# v2_Sandwich_8_bit_waves.net
KiCad netlist of a schematic drawn in EAGLE
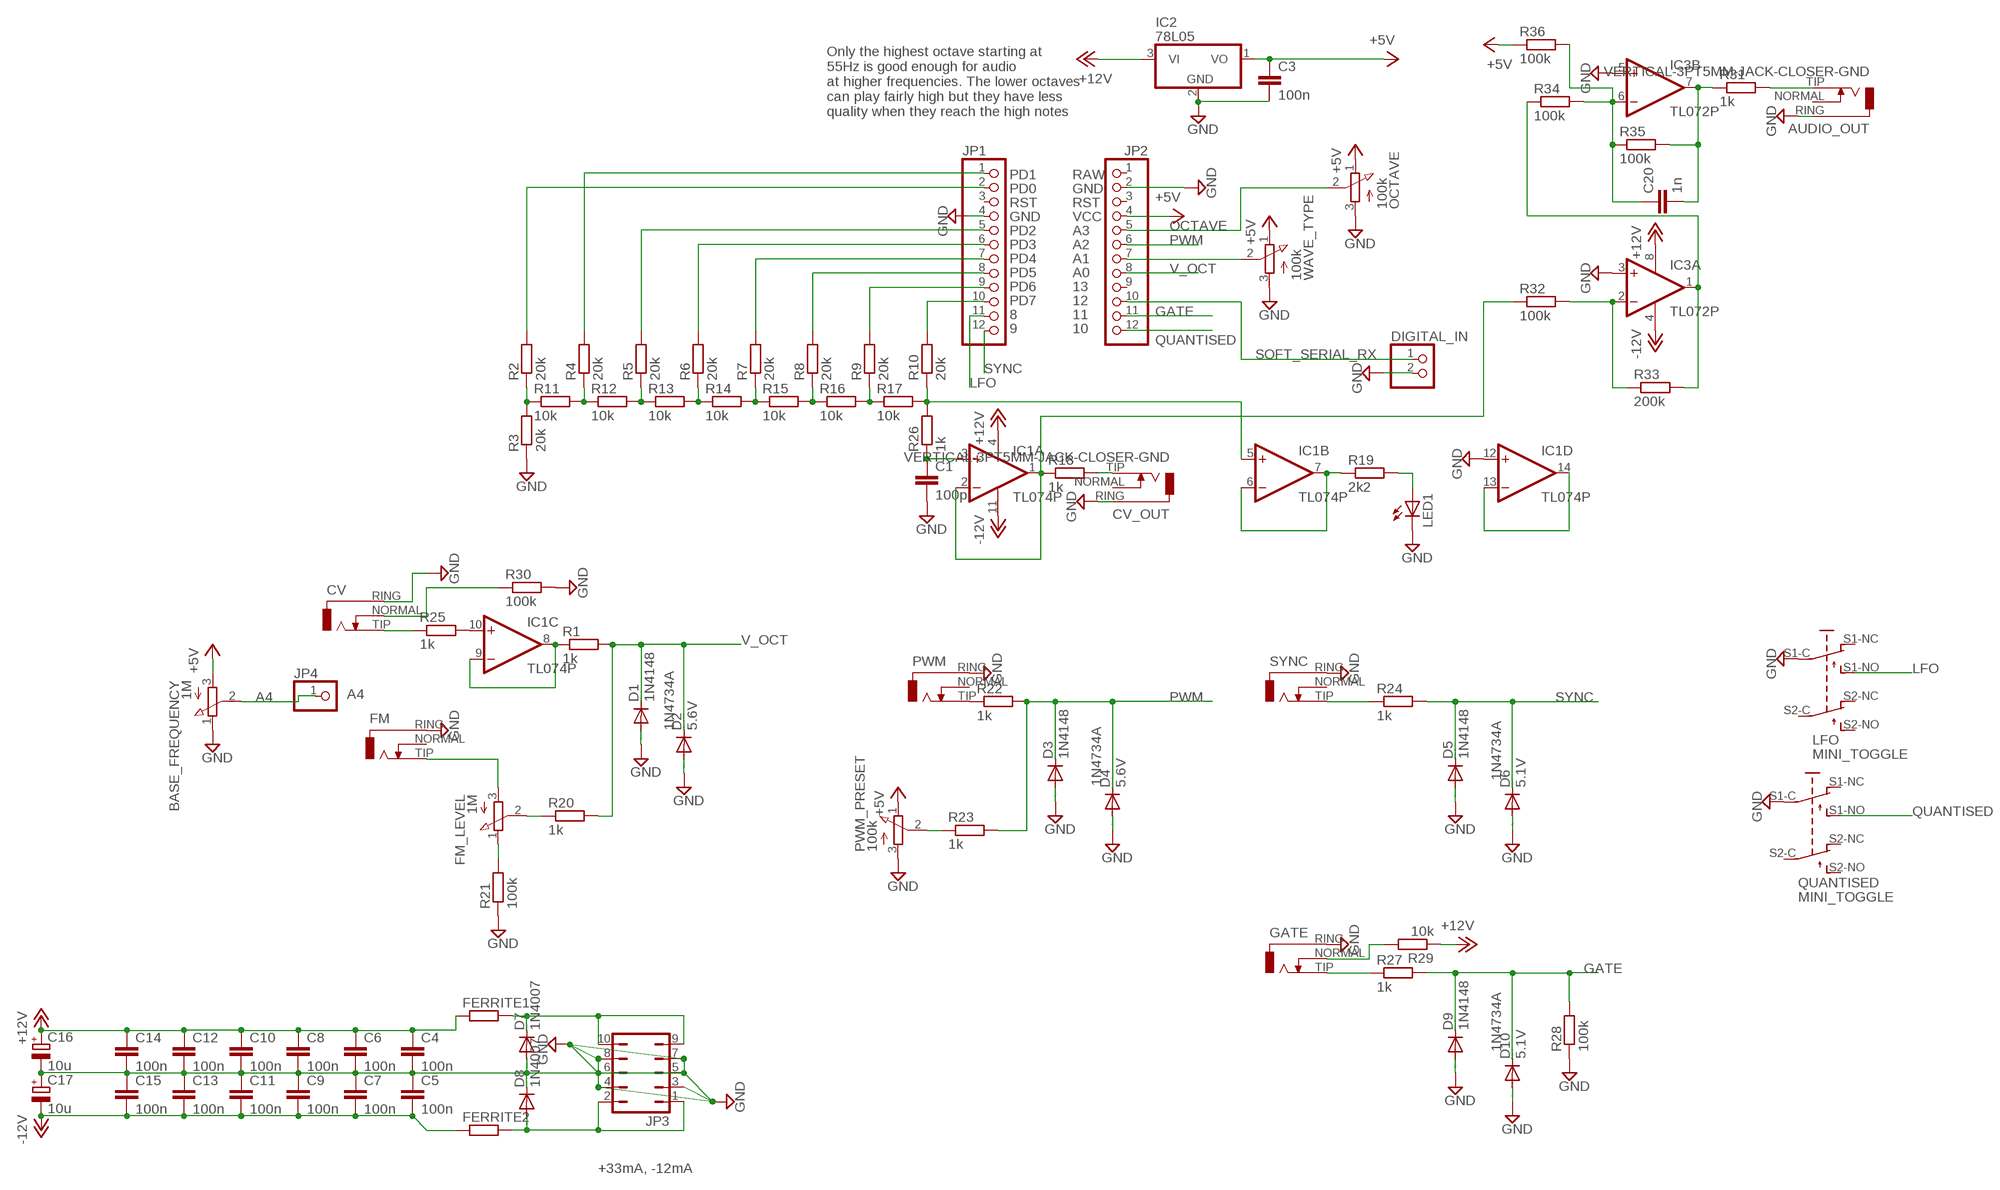
[diagram p0: schematic, sheet 1]

(export (version "E")
  (design (tool "Eeschema 10.0.6"))
  (components
    (comp (ref "AUDIO_OUT")
      (value "VERTICAL-3PT5MM-JACK-CLOSER-GND")
      (footprint "eagle-import:VERTICAL-3PT5MM-JACK-CLOSER-GND")
      (libsource (lib "eagle-import") (part "VERTICAL-3PT5MM-JACK-CLOSER-GND"))
    )
    (comp (ref "BASE_FREQUENCY")
      (value "1M")
      (footprint "eagle-import:EVUF")
      (libsource (lib "eagle-import") (part "9MM_VERT_POT"))
    )
    (comp (ref "C1")
      (value "100p")
      (footprint "eagle-import:C050-024X044")
      (libsource (lib "eagle-import") (part "C-EU050-024X044"))
    )
    (comp (ref "C3")
      (value "100n")
      (footprint "eagle-import:C050-024X044")
      (libsource (lib "eagle-import") (part "C-EU050-024X044"))
    )
    (comp (ref "C4")
      (value "100n")
      (footprint "eagle-import:C050-024X044")
      (libsource (lib "eagle-import") (part "C-EU050-024X044"))
    )
    (comp (ref "C5")
      (value "100n")
      (footprint "eagle-import:C050-024X044")
      (libsource (lib "eagle-import") (part "C-EU050-024X044"))
    )
    (comp (ref "C6")
      (value "100n")
      (footprint "eagle-import:C050-024X044")
      (libsource (lib "eagle-import") (part "C-EU050-024X044"))
    )
    (comp (ref "C7")
      (value "100n")
      (footprint "eagle-import:C050-024X044")
      (libsource (lib "eagle-import") (part "C-EU050-024X044"))
    )
    (comp (ref "C8")
      (value "100n")
      (footprint "eagle-import:C050-024X044")
      (libsource (lib "eagle-import") (part "C-EU050-024X044"))
    )
    (comp (ref "C9")
      (value "100n")
      (footprint "eagle-import:C050-024X044")
      (libsource (lib "eagle-import") (part "C-EU050-024X044"))
    )
    (comp (ref "C10")
      (value "100n")
      (footprint "eagle-import:C050-024X044")
      (libsource (lib "eagle-import") (part "C-EU050-024X044"))
    )
    (comp (ref "C11")
      (value "100n")
      (footprint "eagle-import:C050-024X044")
      (libsource (lib "eagle-import") (part "C-EU050-024X044"))
    )
    (comp (ref "C12")
      (value "100n")
      (footprint "eagle-import:C050-024X044")
      (libsource (lib "eagle-import") (part "C-EU050-024X044"))
    )
    (comp (ref "C13")
      (value "100n")
      (footprint "eagle-import:C050-024X044")
      (libsource (lib "eagle-import") (part "C-EU050-024X044"))
    )
    (comp (ref "C14")
      (value "100n")
      (footprint "eagle-import:C050-024X044")
      (libsource (lib "eagle-import") (part "C-EU050-024X044"))
    )
    (comp (ref "C15")
      (value "100n")
      (footprint "eagle-import:C050-024X044")
      (libsource (lib "eagle-import") (part "C-EU050-024X044"))
    )
    (comp (ref "C16")
      (value "10u")
      (footprint "eagle-import:E2,5-5")
      (libsource (lib "eagle-import") (part "CPOL-EUE2.5-5"))
    )
    (comp (ref "C17")
      (value "10u")
      (footprint "eagle-import:E2,5-5")
      (libsource (lib "eagle-import") (part "CPOL-EUE2.5-5"))
    )
    (comp (ref "C20")
      (value "1n")
      (footprint "eagle-import:C050-024X044")
      (libsource (lib "eagle-import") (part "C-EU050-024X044"))
    )
    (comp (ref "CV")
      (value "VERTICAL-3PT5MM-JACK-CLOSER-GND")
      (footprint "eagle-import:VERTICAL-3PT5MM-JACK-CLOSER-GND")
      (libsource (lib "eagle-import") (part "VERTICAL-3PT5MM-JACK-CLOSER-GND"))
    )
    (comp (ref "CV_OUT")
      (value "VERTICAL-3PT5MM-JACK-CLOSER-GND")
      (footprint "eagle-import:VERTICAL-3PT5MM-JACK-CLOSER-GND")
      (libsource (lib "eagle-import") (part "VERTICAL-3PT5MM-JACK-CLOSER-GND"))
    )
    (comp (ref "D1")
      (value "1N4148")
      (footprint "eagle-import:D-6.35")
      (libsource (lib "eagle-import") (part "1N914"))
    )
    (comp (ref "D2")
      (value "5.6V")
      (footprint "eagle-import:DO41-10")
      (libsource (lib "eagle-import") (part "1N4004"))
    )
    (comp (ref "D3")
      (value "1N4148")
      (footprint "eagle-import:D-6.35")
      (libsource (lib "eagle-import") (part "1N914"))
    )
    (comp (ref "D4")
      (value "5.6V")
      (footprint "eagle-import:DO41-10")
      (libsource (lib "eagle-import") (part "1N4004"))
    )
    (comp (ref "D5")
      (value "1N4148")
      (footprint "eagle-import:D-6.35")
      (libsource (lib "eagle-import") (part "1N914"))
    )
    (comp (ref "D6")
      (value "5.1V")
      (footprint "eagle-import:DO41-10")
      (libsource (lib "eagle-import") (part "1N4004"))
    )
    (comp (ref "D7")
      (value "1N4007")
      (footprint "eagle-import:DO41-10")
      (libsource (lib "eagle-import") (part "1N4004"))
    )
    (comp (ref "D8")
      (value "1N4007")
      (footprint "eagle-import:DO41-10")
      (libsource (lib "eagle-import") (part "1N4004"))
    )
    (comp (ref "D9")
      (value "1N4148")
      (footprint "eagle-import:D-6.35")
      (libsource (lib "eagle-import") (part "1N914"))
    )
    (comp (ref "D10")
      (value "5.1V")
      (footprint "eagle-import:DO41-10")
      (libsource (lib "eagle-import") (part "1N4004"))
    )
    (comp (ref "DIGITAL_IN")
      (value "PINHD-1X2")
      (footprint "eagle-import:1X02")
      (libsource (lib "eagle-import") (part "PINHD-1X2"))
    )
    (comp (ref "FERRITE1")
      (value "R-EU_0204/7")
      (footprint "eagle-import:0204_7")
      (libsource (lib "eagle-import") (part "R-EU_0204/7"))
    )
    (comp (ref "FERRITE2")
      (value "R-EU_0204/7")
      (footprint "eagle-import:0204_7")
      (libsource (lib "eagle-import") (part "R-EU_0204/7"))
    )
    (comp (ref "FM")
      (value "VERTICAL-3PT5MM-JACK-CLOSER-GND")
      (footprint "eagle-import:VERTICAL-3PT5MM-JACK-CLOSER-GND")
      (libsource (lib "eagle-import") (part "VERTICAL-3PT5MM-JACK-CLOSER-GND"))
    )
    (comp (ref "FM_LEVEL")
      (value "1M")
      (footprint "eagle-import:EVUF")
      (libsource (lib "eagle-import") (part "9MM_VERT_POT"))
    )
    (comp (ref "GATE")
      (value "VERTICAL-3PT5MM-JACK-CLOSER-GND")
      (footprint "eagle-import:VERTICAL-3PT5MM-JACK-CLOSER-GND")
      (libsource (lib "eagle-import") (part "VERTICAL-3PT5MM-JACK-CLOSER-GND"))
    )
    (comp (ref "IC1")
      (value "TL074P")
      (footprint "eagle-import:DIL14")
      (libsource (lib "eagle-import") (part "TL074P"))
    )
    (comp (ref "IC2")
      (value "78L05")
      (footprint "eagle-import:TO92")
      (libsource (lib "eagle-import") (part "78ZL05"))
    )
    (comp (ref "IC3")
      (value "TL072P")
      (footprint "eagle-import:DIL08")
      (libsource (lib "eagle-import") (part "TL072P"))
    )
    (comp (ref "JP1")
      (value "PINHD-1X12")
      (footprint "eagle-import:1X12")
      (libsource (lib "eagle-import") (part "PINHD-1X12"))
    )
    (comp (ref "JP2")
      (value "PINHD-1X12")
      (footprint "eagle-import:1X12")
      (libsource (lib "eagle-import") (part "PINHD-1X12"))
    )
    (comp (ref "JP3")
      (value "JP5Q")
      (footprint "eagle-import:JP5Q")
      (libsource (lib "eagle-import") (part "JP5Q"))
    )
    (comp (ref "JP4")
      (value "PINHD-1X1")
      (footprint "eagle-import:1X01")
      (libsource (lib "eagle-import") (part "PINHD-1X1"))
    )
    (comp (ref "LED1")
      (value "LED3MM-NB")
      (footprint "eagle-import:LED3MM")
      (libsource (lib "eagle-import") (part "LED3MM-NB"))
    )
    (comp (ref "LFO")
      (value "MINI_TOGGLE")
      (footprint "eagle-import:MINI_TOGGLE")
      (libsource (lib "eagle-import") (part "MINI_TOGGLE"))
    )
    (comp (ref "OCTAVE")
      (value "100k")
      (footprint "eagle-import:EVUF")
      (libsource (lib "eagle-import") (part "9MM_VERT_POT"))
    )
    (comp (ref "PWM")
      (value "VERTICAL-3PT5MM-JACK-CLOSER-GND")
      (footprint "eagle-import:VERTICAL-3PT5MM-JACK-CLOSER-GND")
      (libsource (lib "eagle-import") (part "VERTICAL-3PT5MM-JACK-CLOSER-GND"))
    )
    (comp (ref "PWM_PRESET")
      (value "100k")
      (footprint "eagle-import:EVUF")
      (libsource (lib "eagle-import") (part "9MM_VERT_POT"))
    )
    (comp (ref "QUANTISED")
      (value "MINI_TOGGLE")
      (footprint "eagle-import:MINI_TOGGLE")
      (libsource (lib "eagle-import") (part "MINI_TOGGLE"))
    )
    (comp (ref "R1")
      (value "1k")
      (footprint "eagle-import:0204_7")
      (libsource (lib "eagle-import") (part "R-EU_0204/7"))
    )
    (comp (ref "R2")
      (value "20k")
      (footprint "eagle-import:0204_7")
      (libsource (lib "eagle-import") (part "R-EU_0204/7"))
    )
    (comp (ref "R3")
      (value "20k")
      (footprint "eagle-import:0204_7")
      (libsource (lib "eagle-import") (part "R-EU_0204/7"))
    )
    (comp (ref "R4")
      (value "20k")
      (footprint "eagle-import:0204_7")
      (libsource (lib "eagle-import") (part "R-EU_0204/7"))
    )
    (comp (ref "R5")
      (value "20k")
      (footprint "eagle-import:0204_7")
      (libsource (lib "eagle-import") (part "R-EU_0204/7"))
    )
    (comp (ref "R6")
      (value "20k")
      (footprint "eagle-import:0204_7")
      (libsource (lib "eagle-import") (part "R-EU_0204/7"))
    )
    (comp (ref "R7")
      (value "20k")
      (footprint "eagle-import:0204_7")
      (libsource (lib "eagle-import") (part "R-EU_0204/7"))
    )
    (comp (ref "R8")
      (value "20k")
      (footprint "eagle-import:0204_7")
      (libsource (lib "eagle-import") (part "R-EU_0204/7"))
    )
    (comp (ref "R9")
      (value "20k")
      (footprint "eagle-import:0204_7")
      (libsource (lib "eagle-import") (part "R-EU_0204/7"))
    )
    (comp (ref "R10")
      (value "20k")
      (footprint "eagle-import:0204_7")
      (libsource (lib "eagle-import") (part "R-EU_0204/7"))
    )
    (comp (ref "R11")
      (value "10k")
      (footprint "eagle-import:0204_7")
      (libsource (lib "eagle-import") (part "R-EU_0204/7"))
    )
    (comp (ref "R12")
      (value "10k")
      (footprint "eagle-import:0204_7")
      (libsource (lib "eagle-import") (part "R-EU_0204/7"))
    )
    (comp (ref "R13")
      (value "10k")
      (footprint "eagle-import:0204_7")
      (libsource (lib "eagle-import") (part "R-EU_0204/7"))
    )
    (comp (ref "R14")
      (value "10k")
      (footprint "eagle-import:0204_7")
      (libsource (lib "eagle-import") (part "R-EU_0204/7"))
    )
    (comp (ref "R15")
      (value "10k")
      (footprint "eagle-import:0204_7")
      (libsource (lib "eagle-import") (part "R-EU_0204/7"))
    )
    (comp (ref "R16")
      (value "10k")
      (footprint "eagle-import:0204_7")
      (libsource (lib "eagle-import") (part "R-EU_0204/7"))
    )
    (comp (ref "R17")
      (value "10k")
      (footprint "eagle-import:0204_7")
      (libsource (lib "eagle-import") (part "R-EU_0204/7"))
    )
    (comp (ref "R18")
      (value "1k")
      (footprint "eagle-import:0204_7")
      (libsource (lib "eagle-import") (part "R-EU_0204/7"))
    )
    (comp (ref "R19")
      (value "2k2")
      (footprint "eagle-import:0204_7")
      (libsource (lib "eagle-import") (part "R-EU_0204/7"))
    )
    (comp (ref "R20")
      (value "1k")
      (footprint "eagle-import:0204_7")
      (libsource (lib "eagle-import") (part "R-EU_0204/7"))
    )
    (comp (ref "R21")
      (value "100k")
      (footprint "eagle-import:0204_7")
      (libsource (lib "eagle-import") (part "R-EU_0204/7"))
    )
    (comp (ref "R22")
      (value "1k")
      (footprint "eagle-import:0204_7")
      (libsource (lib "eagle-import") (part "R-EU_0204/7"))
    )
    (comp (ref "R23")
      (value "1k")
      (footprint "eagle-import:0204_7")
      (libsource (lib "eagle-import") (part "R-EU_0204/7"))
    )
    (comp (ref "R24")
      (value "1k")
      (footprint "eagle-import:0204_7")
      (libsource (lib "eagle-import") (part "R-EU_0204/7"))
    )
    (comp (ref "R25")
      (value "1k")
      (footprint "eagle-import:0204_7")
      (libsource (lib "eagle-import") (part "R-EU_0204/7"))
    )
    (comp (ref "R26")
      (value "1k")
      (footprint "eagle-import:0204_7")
      (libsource (lib "eagle-import") (part "R-EU_0204/7"))
    )
    (comp (ref "R27")
      (value "1k")
      (footprint "eagle-import:0204_7")
      (libsource (lib "eagle-import") (part "R-EU_0204/7"))
    )
    (comp (ref "R28")
      (value "100k")
      (footprint "eagle-import:0204_7")
      (libsource (lib "eagle-import") (part "R-EU_0204/7"))
    )
    (comp (ref "R29")
      (value "10k")
      (footprint "eagle-import:0204_7")
      (libsource (lib "eagle-import") (part "R-EU_0204/7"))
    )
    (comp (ref "R30")
      (value "100k")
      (footprint "eagle-import:0204_7")
      (libsource (lib "eagle-import") (part "R-EU_0204/7"))
    )
    (comp (ref "R31")
      (value "1k")
      (footprint "eagle-import:0204_7")
      (libsource (lib "eagle-import") (part "R-EU_0204/7"))
    )
    (comp (ref "R32")
      (value "100k")
      (footprint "eagle-import:0204_7")
      (libsource (lib "eagle-import") (part "R-EU_0204/7"))
    )
    (comp (ref "R33")
      (value "200k")
      (footprint "eagle-import:0204_7")
      (libsource (lib "eagle-import") (part "R-EU_0204/7"))
    )
    (comp (ref "R34")
      (value "100k")
      (footprint "eagle-import:0204_7")
      (libsource (lib "eagle-import") (part "R-EU_0204/7"))
    )
    (comp (ref "R35")
      (value "100k")
      (footprint "eagle-import:0204_7")
      (libsource (lib "eagle-import") (part "R-EU_0204/7"))
    )
    (comp (ref "R36")
      (value "100k")
      (footprint "eagle-import:0204_7")
      (libsource (lib "eagle-import") (part "R-EU_0204/7"))
    )
    (comp (ref "SYNC")
      (value "VERTICAL-3PT5MM-JACK-CLOSER-GND")
      (footprint "eagle-import:VERTICAL-3PT5MM-JACK-CLOSER-GND")
      (libsource (lib "eagle-import") (part "VERTICAL-3PT5MM-JACK-CLOSER-GND"))
    )
    (comp (ref "WAVE_TYPE")
      (value "100k")
      (footprint "eagle-import:EVUF")
      (libsource (lib "eagle-import") (part "9MM_VERT_POT"))
    )
  )
  (nets
    (net (code "1") (name "+5V") (class "Default")
      (node (ref "BASE_FREQUENCY") (pin "3") (pinfunction "A_3") (pintype "passive"))
      (node (ref "C3") (pin "1") (pinfunction "1_1") (pintype "passive"))
      (node (ref "IC2") (pin "1") (pinfunction "VO_1") (pintype "passive"))
      (node (ref "JP2") (pin "4") (pinfunction "4_4") (pintype "passive"))
      (node (ref "OCTAVE") (pin "1") (pinfunction "E_1") (pintype "passive"))
      (node (ref "PWM_PRESET") (pin "1") (pinfunction "E_1") (pintype "passive"))
      (node (ref "R36") (pin "1") (pinfunction "1_1") (pintype "passive"))
      (node (ref "WAVE_TYPE") (pin "1") (pinfunction "E_1") (pintype "passive"))
    )
    (net (code "2") (name "+12V") (class "Default")
      (node (ref "C10") (pin "1") (pinfunction "1_1") (pintype "passive"))
      (node (ref "C12") (pin "1") (pinfunction "1_1") (pintype "passive"))
      (node (ref "C14") (pin "1") (pinfunction "1_1") (pintype "passive"))
      (node (ref "C16") (pin "+") (pinfunction "+_+") (pintype "passive"))
      (node (ref "C4") (pin "1") (pinfunction "1_1") (pintype "passive"))
      (node (ref "C6") (pin "1") (pinfunction "1_1") (pintype "passive"))
      (node (ref "C8") (pin "1") (pinfunction "1_1") (pintype "passive"))
      (node (ref "FERRITE1") (pin "1") (pinfunction "1_1") (pintype "passive"))
      (node (ref "IC1") (pin "4") (pinfunction "V+_4") (pintype "power_in"))
      (node (ref "IC2") (pin "3") (pinfunction "VI_3") (pintype "input"))
      (node (ref "IC3") (pin "8") (pinfunction "V+_8") (pintype "power_in"))
      (node (ref "R29") (pin "1") (pinfunction "1_1") (pintype "passive"))
    )
    (net (code "3") (name "-12V") (class "Default")
      (node (ref "C11") (pin "2") (pinfunction "2_2") (pintype "passive"))
      (node (ref "C13") (pin "2") (pinfunction "2_2") (pintype "passive"))
      (node (ref "C15") (pin "2") (pinfunction "2_2") (pintype "passive"))
      (node (ref "C17") (pin "-") (pinfunction "-_-") (pintype "passive"))
      (node (ref "C5") (pin "2") (pinfunction "2_2") (pintype "passive"))
      (node (ref "C7") (pin "2") (pinfunction "2_2") (pintype "passive"))
      (node (ref "C9") (pin "2") (pinfunction "2_2") (pintype "passive"))
      (node (ref "FERRITE2") (pin "1") (pinfunction "1_1") (pintype "passive"))
      (node (ref "IC1") (pin "11") (pinfunction "V-_11") (pintype "power_in"))
      (node (ref "IC3") (pin "4") (pinfunction "V-_4") (pintype "power_in"))
    )
    (net (code "4") (name "/A4") (class "Default")
      (node (ref "BASE_FREQUENCY") (pin "2") (pinfunction "S_2") (pintype "passive"))
      (node (ref "JP4") (pin "1") (pinfunction "1_1") (pintype "passive"))
    )
    (net (code "5") (name "/GATE") (class "Default")
      (node (ref "D10") (pin "C") (pinfunction "C_C") (pintype "passive"))
      (node (ref "D9") (pin "C") (pinfunction "C_C") (pintype "passive"))
      (node (ref "JP2") (pin "11") (pinfunction "11_11") (pintype "passive"))
      (node (ref "R27") (pin "2") (pinfunction "2_2") (pintype "passive"))
      (node (ref "R28") (pin "2") (pinfunction "2_2") (pintype "passive"))
    )
    (net (code "6") (name "/LFO") (class "Default")
      (node (ref "JP1") (pin "11") (pinfunction "11_11") (pintype "passive"))
      (node (ref "LFO") (pin "S1-NO") (pinfunction "S1-NO_S1-NO") (pintype "passive"))
    )
    (net (code "7") (name "/OCTAVE") (class "Default")
      (node (ref "JP2") (pin "5") (pinfunction "5_5") (pintype "passive"))
      (node (ref "OCTAVE") (pin "2") (pinfunction "S_2") (pintype "passive"))
    )
    (net (code "8") (name "/PWM") (class "Default")
      (node (ref "D3") (pin "C") (pinfunction "C_C") (pintype "passive"))
      (node (ref "D4") (pin "C") (pinfunction "C_C") (pintype "passive"))
      (node (ref "JP2") (pin "6") (pinfunction "6_6") (pintype "passive"))
      (node (ref "R22") (pin "2") (pinfunction "2_2") (pintype "passive"))
      (node (ref "R23") (pin "2") (pinfunction "2_2") (pintype "passive"))
    )
    (net (code "9") (name "/QUANTISED") (class "Default")
      (node (ref "JP2") (pin "12") (pinfunction "12_12") (pintype "passive"))
      (node (ref "QUANTISED") (pin "S1-NO") (pinfunction "S1-NO_S1-NO") (pintype "passive"))
    )
    (net (code "10") (name "/SOFT_SERIAL_RX") (class "Default")
      (node (ref "DIGITAL_IN") (pin "1") (pinfunction "1_1") (pintype "passive"))
      (node (ref "JP2") (pin "10") (pinfunction "10_10") (pintype "passive"))
    )
    (net (code "11") (name "/SYNC") (class "Default")
      (node (ref "D5") (pin "C") (pinfunction "C_C") (pintype "passive"))
      (node (ref "D6") (pin "C") (pinfunction "C_C") (pintype "passive"))
      (node (ref "JP1") (pin "12") (pinfunction "12_12") (pintype "passive"))
      (node (ref "R24") (pin "2") (pinfunction "2_2") (pintype "passive"))
    )
    (net (code "12") (name "/V_OCT") (class "Default")
      (node (ref "D1") (pin "C") (pinfunction "C_C") (pintype "passive"))
      (node (ref "D2") (pin "C") (pinfunction "C_C") (pintype "passive"))
      (node (ref "JP2") (pin "8") (pinfunction "8_8") (pintype "passive"))
      (node (ref "R1") (pin "2") (pinfunction "2_2") (pintype "passive"))
      (node (ref "R20") (pin "2") (pinfunction "2_2") (pintype "passive"))
    )
    (net (code "13") (name "GND") (class "Default")
      (node (ref "AUDIO_OUT") (pin "RING") (pinfunction "1_RING") (pintype "passive"))
      (node (ref "BASE_FREQUENCY") (pin "1") (pinfunction "E_1") (pintype "passive"))
      (node (ref "C1") (pin "2") (pinfunction "2_2") (pintype "passive"))
      (node (ref "C10") (pin "2") (pinfunction "2_2") (pintype "passive"))
      (node (ref "C11") (pin "1") (pinfunction "1_1") (pintype "passive"))
      (node (ref "C12") (pin "2") (pinfunction "2_2") (pintype "passive"))
      (node (ref "C13") (pin "1") (pinfunction "1_1") (pintype "passive"))
      (node (ref "C14") (pin "2") (pinfunction "2_2") (pintype "passive"))
      (node (ref "C15") (pin "1") (pinfunction "1_1") (pintype "passive"))
      (node (ref "C16") (pin "-") (pinfunction "-_-") (pintype "passive"))
      (node (ref "C17") (pin "+") (pinfunction "+_+") (pintype "passive"))
      (node (ref "C3") (pin "2") (pinfunction "2_2") (pintype "passive"))
      (node (ref "C4") (pin "2") (pinfunction "2_2") (pintype "passive"))
      (node (ref "C5") (pin "1") (pinfunction "1_1") (pintype "passive"))
      (node (ref "C6") (pin "2") (pinfunction "2_2") (pintype "passive"))
      (node (ref "C7") (pin "1") (pinfunction "1_1") (pintype "passive"))
      (node (ref "C8") (pin "2") (pinfunction "2_2") (pintype "passive"))
      (node (ref "C9") (pin "1") (pinfunction "1_1") (pintype "passive"))
      (node (ref "CV") (pin "RING") (pinfunction "1_RING") (pintype "passive"))
      (node (ref "CV_OUT") (pin "RING") (pinfunction "1_RING") (pintype "passive"))
      (node (ref "D1") (pin "A") (pinfunction "A_A") (pintype "passive"))
      (node (ref "D10") (pin "A") (pinfunction "A_A") (pintype "passive"))
      (node (ref "D2") (pin "A") (pinfunction "A_A") (pintype "passive"))
      (node (ref "D3") (pin "A") (pinfunction "A_A") (pintype "passive"))
      (node (ref "D4") (pin "A") (pinfunction "A_A") (pintype "passive"))
      (node (ref "D5") (pin "A") (pinfunction "A_A") (pintype "passive"))
      (node (ref "D6") (pin "A") (pinfunction "A_A") (pintype "passive"))
      (node (ref "D7") (pin "A") (pinfunction "A_A") (pintype "passive"))
      (node (ref "D8") (pin "C") (pinfunction "C_C") (pintype "passive"))
      (node (ref "D9") (pin "A") (pinfunction "A_A") (pintype "passive"))
      (node (ref "DIGITAL_IN") (pin "2") (pinfunction "2_2") (pintype "passive"))
      (node (ref "FM") (pin "RING") (pinfunction "1_RING") (pintype "passive"))
      (node (ref "GATE") (pin "RING") (pinfunction "1_RING") (pintype "passive"))
      (node (ref "IC1") (pin "12") (pinfunction "+IN_12") (pintype "input"))
      (node (ref "IC2") (pin "2") (pinfunction "GND_2") (pintype "passive"))
      (node (ref "IC3") (pin "3") (pinfunction "+IN_3") (pintype "input"))
      (node (ref "IC3") (pin "5") (pinfunction "+IN_5") (pintype "input"))
      (node (ref "JP1") (pin "4") (pinfunction "4_4") (pintype "passive"))
      (node (ref "JP2") (pin "2") (pinfunction "2_2") (pintype "passive"))
      (node (ref "JP3") (pin "3") (pinfunction "3_3") (pintype "passive"))
      (node (ref "JP3") (pin "4") (pinfunction "4_4") (pintype "passive"))
      (node (ref "JP3") (pin "5") (pinfunction "5_5") (pintype "passive"))
      (node (ref "JP3") (pin "6") (pinfunction "6_6") (pintype "passive"))
      (node (ref "JP3") (pin "7") (pinfunction "7_7") (pintype "passive"))
      (node (ref "JP3") (pin "8") (pinfunction "8_8") (pintype "passive"))
      (node (ref "LED1") (pin "K") (pinfunction "C_K") (pintype "passive"))
      (node (ref "LFO") (pin "S1-C") (pinfunction "S1-C_S1-C") (pintype "passive"))
      (node (ref "OCTAVE") (pin "3") (pinfunction "A_3") (pintype "passive"))
      (node (ref "PWM") (pin "RING") (pinfunction "1_RING") (pintype "passive"))
      (node (ref "PWM_PRESET") (pin "3") (pinfunction "A_3") (pintype "passive"))
      (node (ref "QUANTISED") (pin "S1-C") (pinfunction "S1-C_S1-C") (pintype "passive"))
      (node (ref "R21") (pin "1") (pinfunction "1_1") (pintype "passive"))
      (node (ref "R28") (pin "1") (pinfunction "1_1") (pintype "passive"))
      (node (ref "R3") (pin "1") (pinfunction "1_1") (pintype "passive"))
      (node (ref "R30") (pin "2") (pinfunction "2_2") (pintype "passive"))
      (node (ref "SYNC") (pin "RING") (pinfunction "1_RING") (pintype "passive"))
      (node (ref "WAVE_TYPE") (pin "3") (pinfunction "A_3") (pintype "passive"))
    )
    (net (code "14") (name "Net-(AUDIO_OUT-3)") (class "Default")
      (node (ref "AUDIO_OUT") (pin "TIP") (pinfunction "3_TIP") (pintype "passive"))
      (node (ref "R31") (pin "2") (pinfunction "2_2") (pintype "passive"))
    )
    (net (code "15") (name "Net-(CV-2)") (class "Default")
      (node (ref "CV") (pin "NORMAL") (pinfunction "2_NORMAL") (pintype "passive"))
      (node (ref "R30") (pin "1") (pinfunction "1_1") (pintype "passive"))
    )
    (net (code "16") (name "Net-(CV-3)") (class "Default")
      (node (ref "CV") (pin "TIP") (pinfunction "3_TIP") (pintype "passive"))
      (node (ref "R25") (pin "1") (pinfunction "1_1") (pintype "passive"))
    )
    (net (code "17") (name "Net-(CV_OUT-3)") (class "Default")
      (node (ref "CV_OUT") (pin "TIP") (pinfunction "3_TIP") (pintype "passive"))
      (node (ref "R18") (pin "2") (pinfunction "2_2") (pintype "passive"))
    )
    (net (code "18") (name "Net-(D7-PadC)") (class "Default")
      (node (ref "D7") (pin "C") (pinfunction "C_C") (pintype "passive"))
      (node (ref "FERRITE1") (pin "2") (pinfunction "2_2") (pintype "passive"))
      (node (ref "JP3") (pin "10") (pinfunction "10_10") (pintype "passive"))
      (node (ref "JP3") (pin "9") (pinfunction "9_9") (pintype "passive"))
    )
    (net (code "19") (name "Net-(D8-PadA)") (class "Default")
      (node (ref "D8") (pin "A") (pinfunction "A_A") (pintype "passive"))
      (node (ref "FERRITE2") (pin "2") (pinfunction "2_2") (pintype "passive"))
      (node (ref "JP3") (pin "1") (pinfunction "1_1") (pintype "passive"))
      (node (ref "JP3") (pin "2") (pinfunction "2_2") (pintype "passive"))
    )
    (net (code "20") (name "Net-(FM-3)") (class "Default")
      (node (ref "FM") (pin "TIP") (pinfunction "3_TIP") (pintype "passive"))
      (node (ref "FM_LEVEL") (pin "3") (pinfunction "A_3") (pintype "passive"))
    )
    (net (code "21") (name "Net-(FM_LEVEL-E)") (class "Default")
      (node (ref "FM_LEVEL") (pin "1") (pinfunction "E_1") (pintype "passive"))
      (node (ref "R21") (pin "2") (pinfunction "2_2") (pintype "passive"))
    )
    (net (code "22") (name "Net-(FM_LEVEL-S)") (class "Default")
      (node (ref "FM_LEVEL") (pin "2") (pinfunction "S_2") (pintype "passive"))
      (node (ref "R20") (pin "1") (pinfunction "1_1") (pintype "passive"))
    )
    (net (code "23") (name "Net-(GATE-2)") (class "Default")
      (node (ref "GATE") (pin "NORMAL") (pinfunction "2_NORMAL") (pintype "passive"))
      (node (ref "R29") (pin "2") (pinfunction "2_2") (pintype "passive"))
    )
    (net (code "24") (name "Net-(GATE-3)") (class "Default")
      (node (ref "GATE") (pin "TIP") (pinfunction "3_TIP") (pintype "passive"))
      (node (ref "R27") (pin "1") (pinfunction "1_1") (pintype "passive"))
    )
    (net (code "25") (name "Net-(IC1A-+IN)") (class "Default")
      (node (ref "C1") (pin "1") (pinfunction "1_1") (pintype "passive"))
      (node (ref "IC1") (pin "3") (pinfunction "+IN_3") (pintype "input"))
      (node (ref "R26") (pin "1") (pinfunction "1_1") (pintype "passive"))
    )
    (net (code "26") (name "Net-(IC1A--IN)") (class "Default")
      (node (ref "IC1") (pin "1") (pinfunction "OUT_1") (pintype "output"))
      (node (ref "IC1") (pin "2") (pinfunction "-IN_2") (pintype "input"))
      (node (ref "R18") (pin "1") (pinfunction "1_1") (pintype "passive"))
      (node (ref "R32") (pin "1") (pinfunction "1_1") (pintype "passive"))
    )
    (net (code "27") (name "Net-(IC1B-+IN)") (class "Default")
      (node (ref "IC1") (pin "5") (pinfunction "+IN_5") (pintype "input"))
      (node (ref "R10") (pin "1") (pinfunction "1_1") (pintype "passive"))
      (node (ref "R17") (pin "2") (pinfunction "2_2") (pintype "passive"))
      (node (ref "R26") (pin "2") (pinfunction "2_2") (pintype "passive"))
    )
    (net (code "28") (name "Net-(IC1B--IN)") (class "Default")
      (node (ref "IC1") (pin "6") (pinfunction "-IN_6") (pintype "input"))
      (node (ref "IC1") (pin "7") (pinfunction "OUT_7") (pintype "output"))
      (node (ref "R19") (pin "1") (pinfunction "1_1") (pintype "passive"))
    )
    (net (code "29") (name "Net-(IC1C-+IN)") (class "Default")
      (node (ref "IC1") (pin "10") (pinfunction "+IN_10") (pintype "input"))
      (node (ref "R25") (pin "2") (pinfunction "2_2") (pintype "passive"))
    )
    (net (code "30") (name "Net-(IC1C--IN)") (class "Default")
      (node (ref "IC1") (pin "8") (pinfunction "OUT_8") (pintype "output"))
      (node (ref "IC1") (pin "9") (pinfunction "-IN_9") (pintype "input"))
      (node (ref "R1") (pin "1") (pinfunction "1_1") (pintype "passive"))
    )
    (net (code "31") (name "Net-(IC1D--IN)") (class "Default")
      (node (ref "IC1") (pin "13") (pinfunction "-IN_13") (pintype "input"))
      (node (ref "IC1") (pin "14") (pinfunction "OUT_14") (pintype "output"))
    )
    (net (code "32") (name "Net-(IC3A--IN)") (class "Default")
      (node (ref "IC3") (pin "2") (pinfunction "-IN_2") (pintype "input"))
      (node (ref "R32") (pin "2") (pinfunction "2_2") (pintype "passive"))
      (node (ref "R33") (pin "1") (pinfunction "1_1") (pintype "passive"))
    )
    (net (code "33") (name "Net-(IC3A-OUT)") (class "Default")
      (node (ref "IC3") (pin "1") (pinfunction "OUT_1") (pintype "output"))
      (node (ref "R33") (pin "2") (pinfunction "2_2") (pintype "passive"))
      (node (ref "R34") (pin "1") (pinfunction "1_1") (pintype "passive"))
    )
    (net (code "34") (name "Net-(IC3B--IN)") (class "Default")
      (node (ref "C20") (pin "1") (pinfunction "1_1") (pintype "passive"))
      (node (ref "IC3") (pin "6") (pinfunction "-IN_6") (pintype "input"))
      (node (ref "R34") (pin "2") (pinfunction "2_2") (pintype "passive"))
      (node (ref "R35") (pin "1") (pinfunction "1_1") (pintype "passive"))
      (node (ref "R36") (pin "2") (pinfunction "2_2") (pintype "passive"))
    )
    (net (code "35") (name "Net-(IC3B-OUT)") (class "Default")
      (node (ref "C20") (pin "2") (pinfunction "2_2") (pintype "passive"))
      (node (ref "IC3") (pin "7") (pinfunction "OUT_7") (pintype "output"))
      (node (ref "R31") (pin "1") (pinfunction "1_1") (pintype "passive"))
      (node (ref "R35") (pin "2") (pinfunction "2_2") (pintype "passive"))
    )
    (net (code "36") (name "Net-(JP1-Pad1)") (class "Default")
      (node (ref "JP1") (pin "1") (pinfunction "1_1") (pintype "passive"))
      (node (ref "R4") (pin "2") (pinfunction "2_2") (pintype "passive"))
    )
    (net (code "37") (name "Net-(JP1-Pad2)") (class "Default")
      (node (ref "JP1") (pin "2") (pinfunction "2_2") (pintype "passive"))
      (node (ref "R2") (pin "2") (pinfunction "2_2") (pintype "passive"))
    )
    (net (code "38") (name "Net-(JP1-Pad5)") (class "Default")
      (node (ref "JP1") (pin "5") (pinfunction "5_5") (pintype "passive"))
      (node (ref "R5") (pin "2") (pinfunction "2_2") (pintype "passive"))
    )
    (net (code "39") (name "Net-(JP1-Pad6)") (class "Default")
      (node (ref "JP1") (pin "6") (pinfunction "6_6") (pintype "passive"))
      (node (ref "R6") (pin "2") (pinfunction "2_2") (pintype "passive"))
    )
    (net (code "40") (name "Net-(JP1-Pad7)") (class "Default")
      (node (ref "JP1") (pin "7") (pinfunction "7_7") (pintype "passive"))
      (node (ref "R7") (pin "2") (pinfunction "2_2") (pintype "passive"))
    )
    (net (code "41") (name "Net-(JP1-Pad8)") (class "Default")
      (node (ref "JP1") (pin "8") (pinfunction "8_8") (pintype "passive"))
      (node (ref "R8") (pin "2") (pinfunction "2_2") (pintype "passive"))
    )
    (net (code "42") (name "Net-(JP1-Pad9)") (class "Default")
      (node (ref "JP1") (pin "9") (pinfunction "9_9") (pintype "passive"))
      (node (ref "R9") (pin "2") (pinfunction "2_2") (pintype "passive"))
    )
    (net (code "43") (name "Net-(JP1-Pad10)") (class "Default")
      (node (ref "JP1") (pin "10") (pinfunction "10_10") (pintype "passive"))
      (node (ref "R10") (pin "2") (pinfunction "2_2") (pintype "passive"))
    )
    (net (code "44") (name "Net-(LED1-PadA)") (class "Default")
      (node (ref "LED1") (pin "A") (pinfunction "A_A") (pintype "passive"))
      (node (ref "R19") (pin "2") (pinfunction "2_2") (pintype "passive"))
    )
    (net (code "45") (name "Net-(PWM-3)") (class "Default")
      (node (ref "PWM") (pin "TIP") (pinfunction "3_TIP") (pintype "passive"))
      (node (ref "R22") (pin "1") (pinfunction "1_1") (pintype "passive"))
    )
    (net (code "46") (name "Net-(PWM_PRESET-S)") (class "Default")
      (node (ref "PWM_PRESET") (pin "2") (pinfunction "S_2") (pintype "passive"))
      (node (ref "R23") (pin "1") (pinfunction "1_1") (pintype "passive"))
    )
    (net (code "47") (name "Net-(R11-Pad1)") (class "Default")
      (node (ref "R11") (pin "1") (pinfunction "1_1") (pintype "passive"))
      (node (ref "R2") (pin "1") (pinfunction "1_1") (pintype "passive"))
      (node (ref "R3") (pin "2") (pinfunction "2_2") (pintype "passive"))
    )
    (net (code "48") (name "Net-(R11-Pad2)") (class "Default")
      (node (ref "R11") (pin "2") (pinfunction "2_2") (pintype "passive"))
      (node (ref "R12") (pin "1") (pinfunction "1_1") (pintype "passive"))
      (node (ref "R4") (pin "1") (pinfunction "1_1") (pintype "passive"))
    )
    (net (code "49") (name "Net-(R12-Pad2)") (class "Default")
      (node (ref "R12") (pin "2") (pinfunction "2_2") (pintype "passive"))
      (node (ref "R13") (pin "1") (pinfunction "1_1") (pintype "passive"))
      (node (ref "R5") (pin "1") (pinfunction "1_1") (pintype "passive"))
    )
    (net (code "50") (name "Net-(R13-Pad2)") (class "Default")
      (node (ref "R13") (pin "2") (pinfunction "2_2") (pintype "passive"))
      (node (ref "R14") (pin "1") (pinfunction "1_1") (pintype "passive"))
      (node (ref "R6") (pin "1") (pinfunction "1_1") (pintype "passive"))
    )
    (net (code "51") (name "Net-(R14-Pad2)") (class "Default")
      (node (ref "R14") (pin "2") (pinfunction "2_2") (pintype "passive"))
      (node (ref "R15") (pin "1") (pinfunction "1_1") (pintype "passive"))
      (node (ref "R7") (pin "1") (pinfunction "1_1") (pintype "passive"))
    )
    (net (code "52") (name "Net-(R15-Pad2)") (class "Default")
      (node (ref "R15") (pin "2") (pinfunction "2_2") (pintype "passive"))
      (node (ref "R16") (pin "1") (pinfunction "1_1") (pintype "passive"))
      (node (ref "R8") (pin "1") (pinfunction "1_1") (pintype "passive"))
    )
    (net (code "53") (name "Net-(R16-Pad2)") (class "Default")
      (node (ref "R16") (pin "2") (pinfunction "2_2") (pintype "passive"))
      (node (ref "R17") (pin "1") (pinfunction "1_1") (pintype "passive"))
      (node (ref "R9") (pin "1") (pinfunction "1_1") (pintype "passive"))
    )
    (net (code "54") (name "Net-(SYNC-3)") (class "Default")
      (node (ref "R24") (pin "1") (pinfunction "1_1") (pintype "passive"))
      (node (ref "SYNC") (pin "TIP") (pinfunction "3_TIP") (pintype "passive"))
    )
    (net (code "55") (name "Net-(WAVE_TYPE-S)") (class "Default")
      (node (ref "JP2") (pin "7") (pinfunction "7_7") (pintype "passive"))
      (node (ref "WAVE_TYPE") (pin "2") (pinfunction "S_2") (pintype "passive"))
    )
    (net (code "56") (name "unconnected-(AUDIO_OUT-2-PadNORMAL)") (class "Default")
      (node (ref "AUDIO_OUT") (pin "NORMAL") (pinfunction "2_NORMAL") (pintype "passive"))
    )
    (net (code "57") (name "unconnected-(CV_OUT-2-PadNORMAL)") (class "Default")
      (node (ref "CV_OUT") (pin "NORMAL") (pinfunction "2_NORMAL") (pintype "passive"))
    )
    (net (code "58") (name "unconnected-(FM-2-PadNORMAL)") (class "Default")
      (node (ref "FM") (pin "NORMAL") (pinfunction "2_NORMAL") (pintype "passive"))
    )
    (net (code "59") (name "unconnected-(JP1-Pad3)") (class "Default")
      (node (ref "JP1") (pin "3") (pinfunction "3_3") (pintype "passive"))
    )
    (net (code "60") (name "unconnected-(JP2-Pad1)") (class "Default")
      (node (ref "JP2") (pin "1") (pinfunction "1_1") (pintype "passive"))
    )
    (net (code "61") (name "unconnected-(JP2-Pad3)") (class "Default")
      (node (ref "JP2") (pin "3") (pinfunction "3_3") (pintype "passive"))
    )
    (net (code "62") (name "unconnected-(JP2-Pad9)") (class "Default")
      (node (ref "JP2") (pin "9") (pinfunction "9_9") (pintype "passive"))
    )
    (net (code "63") (name "unconnected-(LFO-PadS1-NC)") (class "Default")
      (node (ref "LFO") (pin "S1-NC") (pinfunction "S1-NC_S1-NC") (pintype "passive"))
    )
    (net (code "64") (name "unconnected-(LFO-PadS2-C)") (class "Default")
      (node (ref "LFO") (pin "S2-C") (pinfunction "S2-C_S2-C") (pintype "passive"))
    )
    (net (code "65") (name "unconnected-(LFO-PadS2-NC)") (class "Default")
      (node (ref "LFO") (pin "S2-NC") (pinfunction "S2-NC_S2-NC") (pintype "passive"))
    )
    (net (code "66") (name "unconnected-(LFO-PadS2-NO)") (class "Default")
      (node (ref "LFO") (pin "S2-NO") (pinfunction "S2-NO_S2-NO") (pintype "passive"))
    )
    (net (code "67") (name "unconnected-(PWM-2-PadNORMAL)") (class "Default")
      (node (ref "PWM") (pin "NORMAL") (pinfunction "2_NORMAL") (pintype "passive"))
    )
    (net (code "68") (name "unconnected-(QUANTISED-PadS1-NC)") (class "Default")
      (node (ref "QUANTISED") (pin "S1-NC") (pinfunction "S1-NC_S1-NC") (pintype "passive"))
    )
    (net (code "69") (name "unconnected-(QUANTISED-PadS2-C)") (class "Default")
      (node (ref "QUANTISED") (pin "S2-C") (pinfunction "S2-C_S2-C") (pintype "passive"))
    )
    (net (code "70") (name "unconnected-(QUANTISED-PadS2-NC)") (class "Default")
      (node (ref "QUANTISED") (pin "S2-NC") (pinfunction "S2-NC_S2-NC") (pintype "passive"))
    )
    (net (code "71") (name "unconnected-(QUANTISED-PadS2-NO)") (class "Default")
      (node (ref "QUANTISED") (pin "S2-NO") (pinfunction "S2-NO_S2-NO") (pintype "passive"))
    )
    (net (code "72") (name "unconnected-(SYNC-2-PadNORMAL)") (class "Default")
      (node (ref "SYNC") (pin "NORMAL") (pinfunction "2_NORMAL") (pintype "passive"))
    )
  )
)
